# BuckAndOutputCircuits_Page_2.net
KiCad netlist of a schematic drawn in Altium Designer
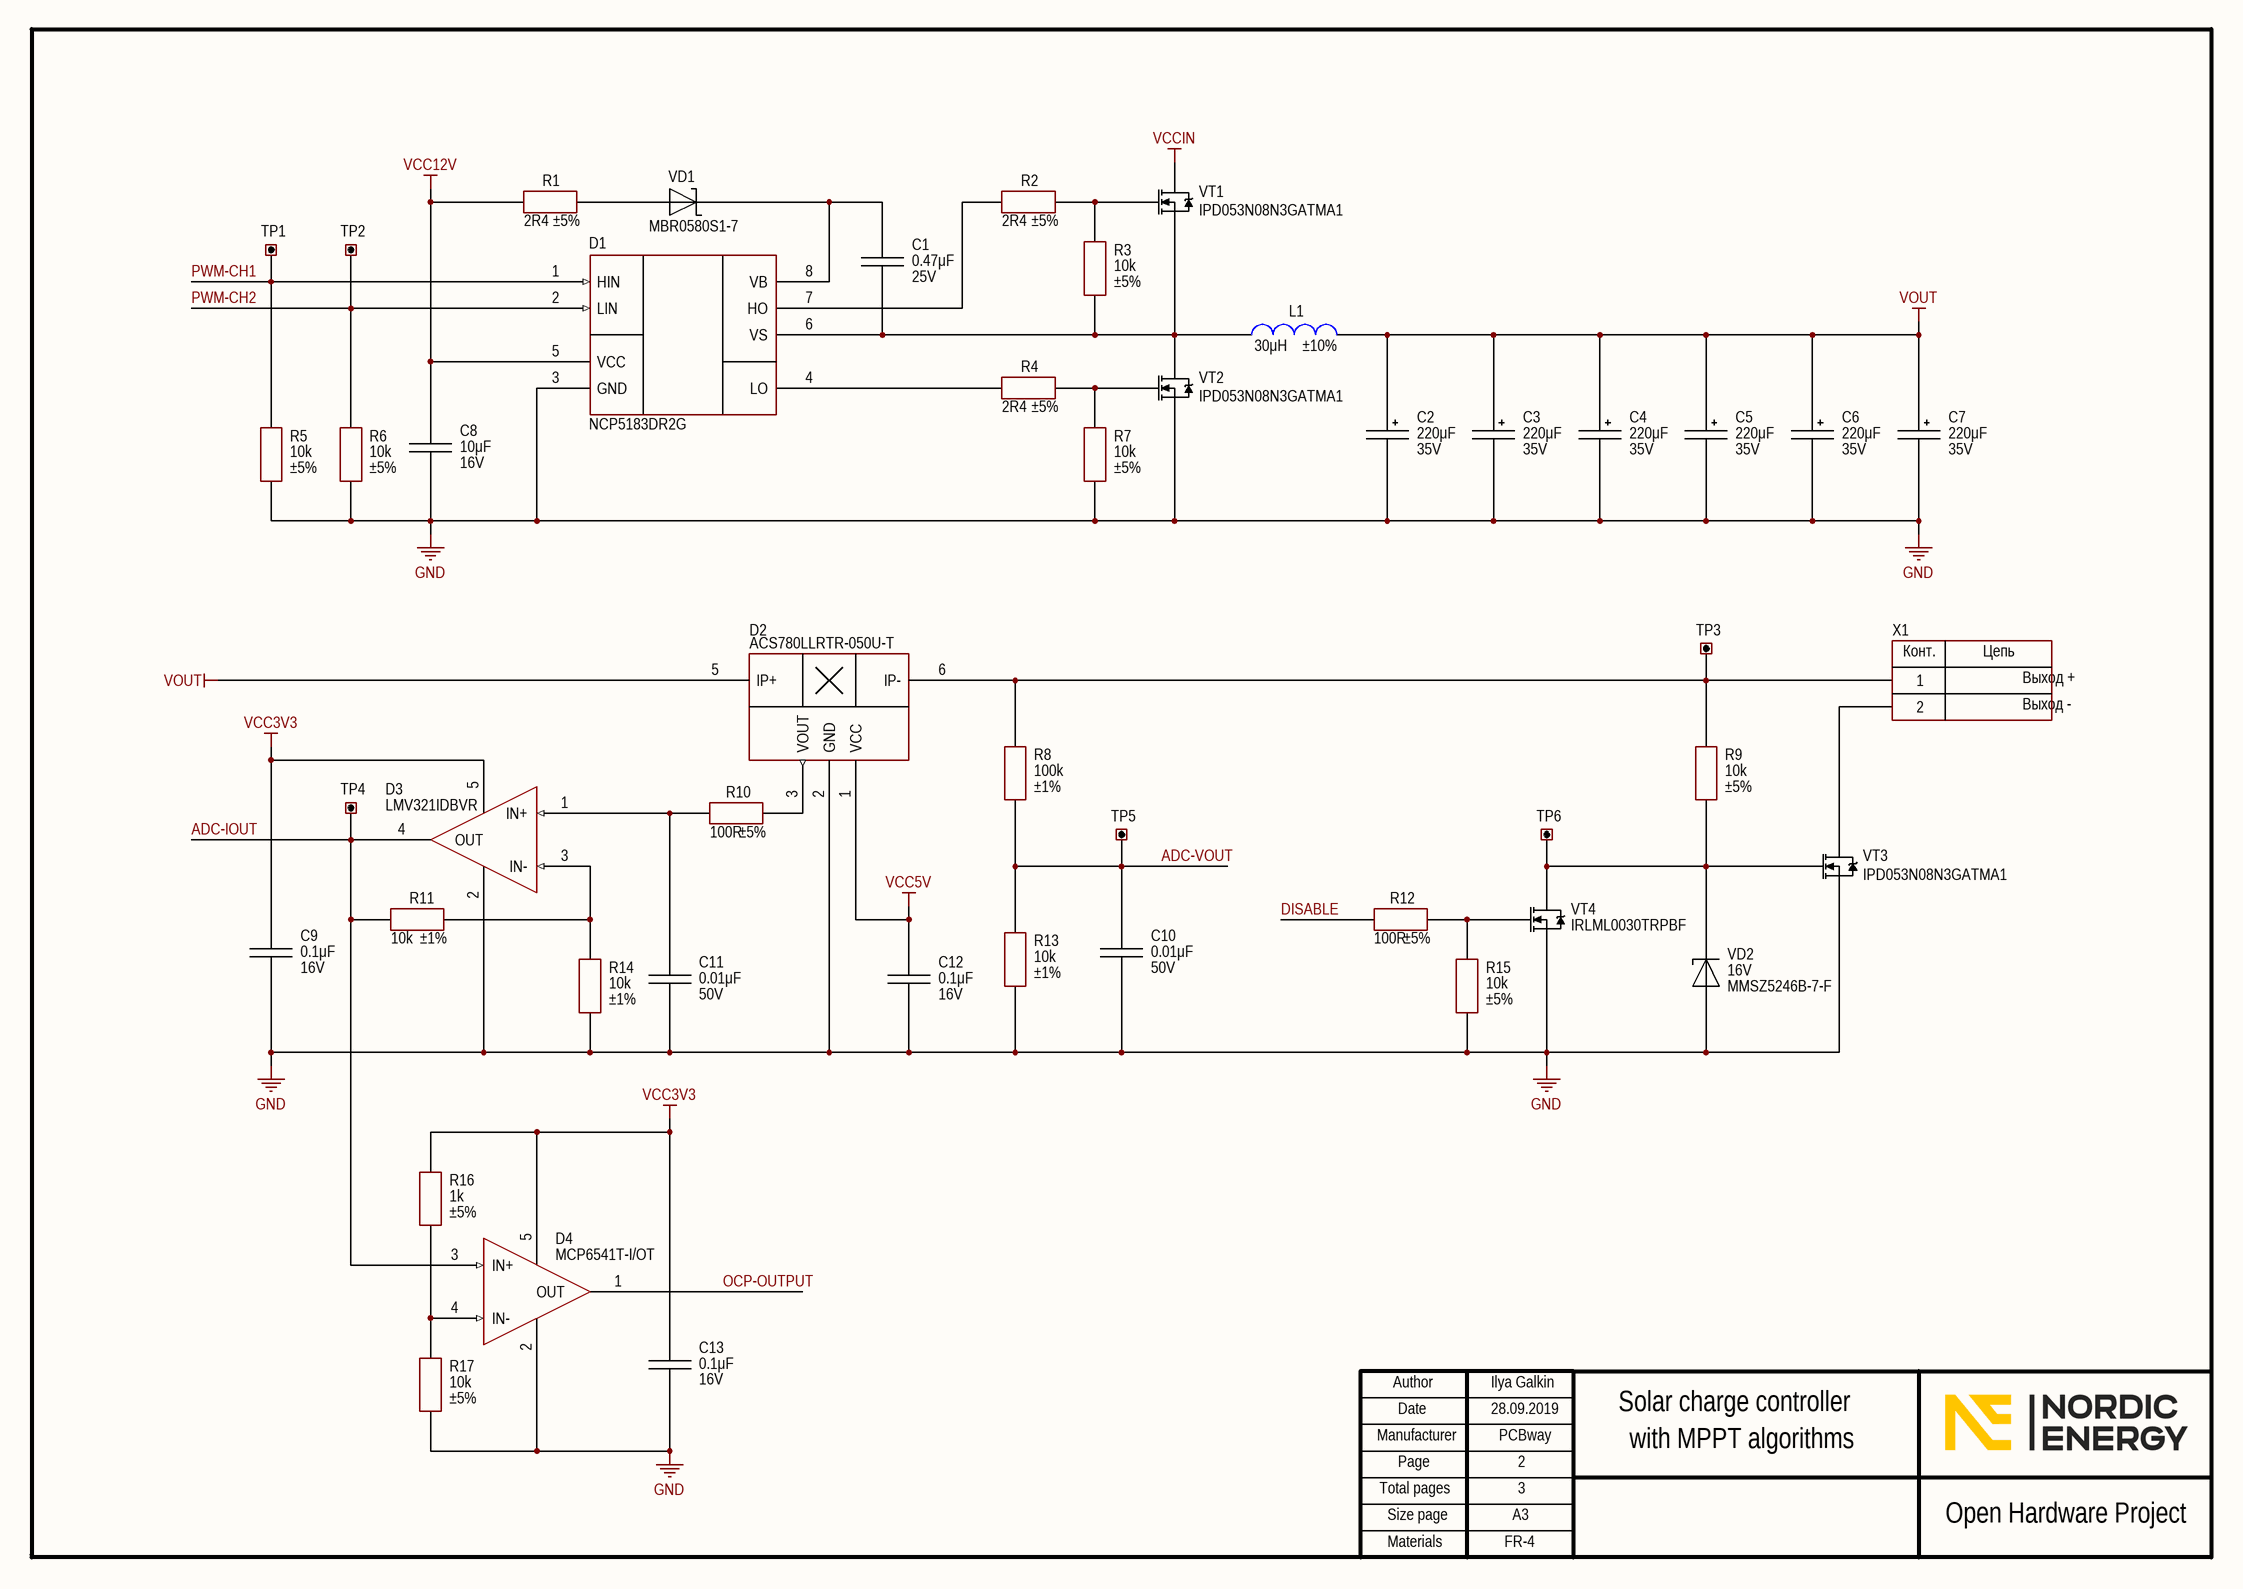
[diagram p0: BuckAndOutputCircuits. Page 2.SchDoc]

(export (version "E")
  (design (tool "Eeschema 10.0.6"))
  (components
    (comp (ref "C1")
      (value "0.47μF")
      (footprint "CAP: 0805")
      (fields
        (field (name "MANUFACTURER") "Yageo")
        (field (name "PARTNUMBER") "CC0805KKX7R8BB474")
        (field (name "VALUEMANUFACTURERPARTNUMBER") "Ceramic capacitor, 0.47μF, X7R, ±10%, 25V, 0805, -55...+125°C")
        (field (name "VOLTAGE") "25V")
      )
      (libsource (lib "Capacitor") (part "Ceramic_0805"))
    )
    (comp (ref "C2")
      (value "220μF")
      (footprint "CAP: D6.3C2.5H11")
      (fields
        (field (name "MANUFACTURER") "Aihua Group")
        (field (name "PARTNUMBER") "SPZ1VM221E12O00")
        (field (name "VALUEMANUFACTURERPARTNUMBER") "Aluminium polymer capacitor, 220μF, 35V, ±20%, 30mOhm, 12x6.3x2.5 mm, -55...+105°C")
        (field (name "VOLTAGE") "35V")
      )
      (libsource (lib "Capacitor") (part "Aluminium"))
    )
    (comp (ref "C3")
      (value "220μF")
      (footprint "CAP: D6.3C2.5H11")
      (fields
        (field (name "MANUFACTURER") "Aihua Group")
        (field (name "PARTNUMBER") "SPZ1VM221E12O00")
        (field (name "VALUEMANUFACTURERPARTNUMBER") "Aluminium polymer capacitor, 220μF, 35V, ±20%, 30mOhm, 12x6.3x2.5 mm, -55...+105°C")
        (field (name "VOLTAGE") "35V")
      )
      (libsource (lib "Capacitor") (part "Aluminium"))
    )
    (comp (ref "C4")
      (value "220μF")
      (footprint "CAP: D6.3C2.5H11")
      (fields
        (field (name "MANUFACTURER") "Aihua Group")
        (field (name "PARTNUMBER") "SPZ1VM221E12O00")
        (field (name "VALUEMANUFACTURERPARTNUMBER") "Aluminium polymer capacitor, 220μF, 35V, ±20%, 30mOhm, 12x6.3x2.5 mm, -55...+105°C")
        (field (name "VOLTAGE") "35V")
      )
      (libsource (lib "Capacitor") (part "Aluminium"))
    )
    (comp (ref "C5")
      (value "220μF")
      (footprint "CAP: D6.3C2.5H11")
      (fields
        (field (name "MANUFACTURER") "Aihua Group")
        (field (name "PARTNUMBER") "SPZ1VM221E12O00")
        (field (name "VALUEMANUFACTURERPARTNUMBER") "Aluminium polymer capacitor, 220μF, 35V, ±20%, 30mOhm, 12x6.3x2.5 mm, -55...+105°C")
        (field (name "VOLTAGE") "35V")
      )
      (libsource (lib "Capacitor") (part "Aluminium"))
    )
    (comp (ref "C6")
      (value "220μF")
      (footprint "CAP: D6.3C2.5H11")
      (fields
        (field (name "MANUFACTURER") "Aihua Group")
        (field (name "PARTNUMBER") "SPZ1VM221E12O00")
        (field (name "VALUEMANUFACTURERPARTNUMBER") "Aluminium polymer capacitor, 220μF, 35V, ±20%, 30mOhm, 12x6.3x2.5 mm, -55...+105°C")
        (field (name "VOLTAGE") "35V")
      )
      (libsource (lib "Capacitor") (part "Aluminium"))
    )
    (comp (ref "C7")
      (value "220μF")
      (footprint "CAP: D6.3C2.5H11")
      (fields
        (field (name "MANUFACTURER") "Aihua Group")
        (field (name "PARTNUMBER") "SPZ1VM221E12O00")
        (field (name "VALUEMANUFACTURERPARTNUMBER") "Aluminium polymer capacitor, 220μF, 35V, ±20%, 30mOhm, 12x6.3x2.5 mm, -55...+105°C")
        (field (name "VOLTAGE") "35V")
      )
      (libsource (lib "Capacitor") (part "Aluminium"))
    )
    (comp (ref "C8")
      (value "10μF")
      (footprint "CAP: 0805")
      (fields
        (field (name "MANUFACTURER") "Samsung")
        (field (name "PARTNUMBER") "CL21B106KOQNNNG")
        (field (name "VALUEMANUFACTURERPARTNUMBER") "Ceramic capacitor, 10μF, X7R, ±10%, 16V, 0805, -55...+125°C")
        (field (name "VOLTAGE") "16V")
      )
      (libsource (lib "Capacitor") (part "Ceramic_0805"))
    )
    (comp (ref "C9")
      (value "0.1μF")
      (footprint "CAP: 0805")
      (fields
        (field (name "MANUFACTURER") "Yageo")
        (field (name "PARTNUMBER") "CC0805KRX7R7BB104")
        (field (name "VALUEMANUFACTURERPARTNUMBER") "Ceramic capacitor, 0.1μF, X7R, ±10%, 16V, 0805, -55...+125°C")
        (field (name "VOLTAGE") "16V")
      )
      (libsource (lib "Capacitor") (part "Ceramic_0805"))
    )
    (comp (ref "C10")
      (value "0.01μF")
      (footprint "CAP: 0805")
      (fields
        (field (name "MANUFACTURER") "Yageo")
        (field (name "PARTNUMBER") "CC0805KRX7R9BB103")
        (field (name "VALUEMANUFACTURERPARTNUMBER") "Ceramic capacitor, 0.01μF, X7R, ±10%, 50V, 0805, -55...+125°C")
        (field (name "VOLTAGE") "50V")
      )
      (libsource (lib "Capacitor") (part "Ceramic_0805"))
    )
    (comp (ref "C11")
      (value "0.01μF")
      (footprint "CAP: 0805")
      (fields
        (field (name "MANUFACTURER") "Yageo")
        (field (name "PARTNUMBER") "CC0805KRX7R9BB103")
        (field (name "VALUEMANUFACTURERPARTNUMBER") "Ceramic capacitor, 0.01μF, X7R, ±10%, 50V, 0805, -55...+125°C")
        (field (name "VOLTAGE") "50V")
      )
      (libsource (lib "Capacitor") (part "Ceramic_0805"))
    )
    (comp (ref "C12")
      (value "0.1μF")
      (footprint "CAP: 0805")
      (fields
        (field (name "MANUFACTURER") "Yageo")
        (field (name "PARTNUMBER") "CC0805KRX7R7BB104")
        (field (name "VALUEMANUFACTURERPARTNUMBER") "Ceramic capacitor, 0.1μF, X7R, ±10%, 16V, 0805, -55...+125°C")
        (field (name "VOLTAGE") "16V")
      )
      (libsource (lib "Capacitor") (part "Ceramic_0805"))
    )
    (comp (ref "C13")
      (value "0.1μF")
      (footprint "CAP: 0805")
      (fields
        (field (name "MANUFACTURER") "Yageo")
        (field (name "PARTNUMBER") "CC0805KRX7R7BB104")
        (field (name "VALUEMANUFACTURERPARTNUMBER") "Ceramic capacitor, 0.1μF, X7R, ±10%, 16V, 0805, -55...+125°C")
        (field (name "VOLTAGE") "16V")
      )
      (libsource (lib "Capacitor") (part "Ceramic_0805"))
    )
    (comp (ref "D1")
      (value "~")
      (footprint "8-SOIC")
      (description "Gate driver")
      (fields
        (field (name "MANUFACTURER") "ON Semiconductor")
        (field (name "VALUEMANUFACTURERPARTNUMBER") "Half-bridge gate driver, 600V, 500kHz, ±4.3A, supply 9...18V, -40...+125°C, 8-SOIC")
        (field (name "PARTNUMBER") "NCP5183DR2G")
      )
      (libsource (lib "IC. Gate driver") (part "NCP5183DR2G"))
    )
    (comp (ref "D2")
      (value "~")
      (footprint "SENSOR: ACS781")
      (description "Current sensors")
      (fields
        (field (name "MANUFACTURER") "Allegro MicroSystems")
        (field (name "VALUEMANUFACTURERPARTNUMBER") "IC current sensors, 50A, ±1.5%, 120 kHz, 60mV/A, -40...+150°C, 7-PSOF")
        (field (name "PARTNUMBER") "ACS780LLRTR-050U-T")
      )
      (libsource (lib "IC. Sensor") (part "ACS780"))
    )
    (comp (ref "D3")
      (value "~")
      (footprint "SOT23-5")
      (description "OP amplifier")
      (fields
        (field (name "MANUFACTURER") "Texas Instruments")
        (field (name "VALUEMANUFACTURERPARTNUMBER") "IC op amplifier, Rail-to-Rail, 1 MHz, 2.7...5.5V, -40...+125°C, SOT23-5")
        (field (name "PARTNUMBER") "LMV321IDBVR")
      )
      (libsource (lib "IC. Amplifier") (part "LMV321IDBVR"))
    )
    (comp (ref "D4")
      (value "~")
      (footprint "SOT23-5")
      (description "Comparator")
      (fields
        (field (name "MANUFACTURER") "Microchip Technology")
        (field (name "VALUEMANUFACTURERPARTNUMBER") "IC comparator, Rail-to-Rail, 1.6...5.5V, -40...+85°C, SOT23-5")
        (field (name "PARTNUMBER") "MCP6541T-I/OT")
      )
      (libsource (lib "IC. Comparator") (part "MCP6541T-I/OT"))
    )
    (comp (ref "L1")
      (value "30μH")
      (footprint "IND: R32.8/20.1/10.7 (L)")
      (fields
        (field (name "MANUFACTURER") "Magnetics")
        (field (name "PARTNUMBER") "0077548A7")
        (field (name "VALUEMANUFACTURERPARTNUMBER") "Fixed inductor, 30μH, ±10%, R32.8/20.1/10.7, Kool Mu, µ=125, 127 нГн/витков2")
        (field (name "TOLERANCE") "±10%")
      )
      (libsource (lib "Inductor") (part "Inductor_R32.8/20.1/10.7"))
    )
    (comp (ref "R1")
      (value "2R4")
      (footprint "RES: 0805")
      (fields
        (field (name "MANUFACTURER") "Yageo")
        (field (name "PARTNUMBER") "RC0805JR-072R4L")
        (field (name "VALUEMANUFACTURERPARTNUMBER") "Resistor film, 2R4, ±5%, 0805, 0.125W, -55...+125°C")
        (field (name "TOLERANCE") "±5%")
      )
      (libsource (lib "") (part "Resistor_0805_1"))
    )
    (comp (ref "R2")
      (value "2R4")
      (footprint "RES: 0805")
      (fields
        (field (name "MANUFACTURER") "Yageo")
        (field (name "PARTNUMBER") "RC0805JR-072R4L")
        (field (name "VALUEMANUFACTURERPARTNUMBER") "Resistor film, 2R4, ±5%, 0805, 0.125W, -55...+125°C")
        (field (name "TOLERANCE") "±5%")
      )
      (libsource (lib "") (part "Resistor_0805_1"))
    )
    (comp (ref "R3")
      (value "10k")
      (footprint "RES: 0805")
      (fields
        (field (name "MANUFACTURER") "Yageo")
        (field (name "PARTNUMBER") "RC0805JR-0710KL")
        (field (name "VALUEMANUFACTURERPARTNUMBER") "Resistor film, 10k, ±5%, 0805, 0.125W, -55...+125°C")
        (field (name "TOLERANCE") "±5%")
      )
      (libsource (lib "Resistor") (part "Resistor_0805"))
    )
    (comp (ref "R4")
      (value "2R4")
      (footprint "RES: 0805")
      (fields
        (field (name "MANUFACTURER") "Yageo")
        (field (name "PARTNUMBER") "RC0805JR-072R4L")
        (field (name "VALUEMANUFACTURERPARTNUMBER") "Resistor film, 2R4, ±5%, 0805, 0.125W, -55...+125°C")
        (field (name "TOLERANCE") "±5%")
      )
      (libsource (lib "") (part "Resistor_0805_1"))
    )
    (comp (ref "R5")
      (value "10k")
      (footprint "RES: 0805")
      (fields
        (field (name "MANUFACTURER") "Yageo")
        (field (name "PARTNUMBER") "RC0805JR-0710KL")
        (field (name "VALUEMANUFACTURERPARTNUMBER") "Resistor film, 10k, ±5%, 0805, 0.125W, -55...+125°C")
        (field (name "TOLERANCE") "±5%")
      )
      (libsource (lib "Resistor") (part "Resistor_0805"))
    )
    (comp (ref "R6")
      (value "10k")
      (footprint "RES: 0805")
      (fields
        (field (name "MANUFACTURER") "Yageo")
        (field (name "PARTNUMBER") "RC0805JR-0710KL")
        (field (name "VALUEMANUFACTURERPARTNUMBER") "Resistor film, 10k, ±5%, 0805, 0.125W, -55...+125°C")
        (field (name "TOLERANCE") "±5%")
      )
      (libsource (lib "Resistor") (part "Resistor_0805"))
    )
    (comp (ref "R7")
      (value "10k")
      (footprint "RES: 0805")
      (fields
        (field (name "MANUFACTURER") "Yageo")
        (field (name "PARTNUMBER") "RC0805JR-0710KL")
        (field (name "VALUEMANUFACTURERPARTNUMBER") "Resistor film, 10k, ±5%, 0805, 0.125W, -55...+125°C")
        (field (name "TOLERANCE") "±5%")
      )
      (libsource (lib "Resistor") (part "Resistor_0805"))
    )
    (comp (ref "R8")
      (value "100k")
      (footprint "RES: 0805")
      (fields
        (field (name "MANUFACTURER") "Yageo")
        (field (name "PARTNUMBER") "RC0805FR-07100KL")
        (field (name "VALUEMANUFACTURERPARTNUMBER") "Resistor film, 100k, ±1%, 0805, 0.125W, -55...+125°C")
        (field (name "TOLERANCE") "±1%")
      )
      (libsource (lib "Resistor") (part "Resistor_0805"))
    )
    (comp (ref "R9")
      (value "10k")
      (footprint "RES: 0805")
      (fields
        (field (name "MANUFACTURER") "Yageo")
        (field (name "PARTNUMBER") "RC0805JR-0710KL")
        (field (name "VALUEMANUFACTURERPARTNUMBER") "Resistor film, 10k, ±5%, 0805, 0.125W, -55...+125°C")
        (field (name "TOLERANCE") "±5%")
      )
      (libsource (lib "Resistor") (part "Resistor_0805"))
    )
    (comp (ref "R10")
      (value "100R")
      (footprint "RES: 0805")
      (fields
        (field (name "MANUFACTURER") "Yageo")
        (field (name "PARTNUMBER") "RC0805JR-07100RL")
        (field (name "VALUEMANUFACTURERPARTNUMBER") "Resistor film, 100R, ±5%, 0805, 0.125W, -55...+125°C")
        (field (name "TOLERANCE") "±5%")
      )
      (libsource (lib "") (part "Resistor_0805_1"))
    )
    (comp (ref "R11")
      (value "10k")
      (footprint "RES: 0805")
      (fields
        (field (name "MANUFACTURER") "Yageo")
        (field (name "PARTNUMBER") "RC0805FR-0710KL")
        (field (name "VALUEMANUFACTURERPARTNUMBER") "Resistor film, 10k, ±1%, 0805, 0.125W, -55...+125°C")
        (field (name "TOLERANCE") "±1%")
      )
      (libsource (lib "") (part "Resistor_0805_1"))
    )
    (comp (ref "R12")
      (value "100R")
      (footprint "RES: 0805")
      (fields
        (field (name "MANUFACTURER") "Yageo")
        (field (name "PARTNUMBER") "RC0805JR-07100RL")
        (field (name "VALUEMANUFACTURERPARTNUMBER") "Resistor film, 100R, ±5%, 0805, 0.125W, -55...+125°C")
        (field (name "TOLERANCE") "±5%")
      )
      (libsource (lib "") (part "Resistor_0805_1"))
    )
    (comp (ref "R13")
      (value "10k")
      (footprint "RES: 0805")
      (fields
        (field (name "MANUFACTURER") "Yageo")
        (field (name "PARTNUMBER") "RC0805FR-0710KL")
        (field (name "VALUEMANUFACTURERPARTNUMBER") "Resistor film, 10k, ±1%, 0805, 0.125W, -55...+125°C")
        (field (name "TOLERANCE") "±1%")
      )
      (libsource (lib "Resistor") (part "Resistor_0805"))
    )
    (comp (ref "R14")
      (value "10k")
      (footprint "RES: 0805")
      (fields
        (field (name "MANUFACTURER") "Yageo")
        (field (name "PARTNUMBER") "RC0805FR-0710KL")
        (field (name "VALUEMANUFACTURERPARTNUMBER") "Resistor film, 10k, ±1%, 0805, 0.125W, -55...+125°C")
        (field (name "TOLERANCE") "±1%")
      )
      (libsource (lib "Resistor") (part "Resistor_0805"))
    )
    (comp (ref "R15")
      (value "10k")
      (footprint "RES: 0805")
      (fields
        (field (name "MANUFACTURER") "Yageo")
        (field (name "PARTNUMBER") "RC0805JR-0710KL")
        (field (name "VALUEMANUFACTURERPARTNUMBER") "Resistor film, 10k, ±5%, 0805, 0.125W, -55...+125°C")
        (field (name "TOLERANCE") "±5%")
      )
      (libsource (lib "Resistor") (part "Resistor_0805"))
    )
    (comp (ref "R16")
      (value "1k")
      (footprint "RES: 0805")
      (fields
        (field (name "MANUFACTURER") "Yageo")
        (field (name "PARTNUMBER") "RC0805JR-071KL")
        (field (name "VALUEMANUFACTURERPARTNUMBER") "Resistor film, 1k, ±5%, 0805, 0.125W, -55...+125°C")
        (field (name "TOLERANCE") "±5%")
      )
      (libsource (lib "Resistor") (part "Resistor_0805"))
    )
    (comp (ref "R17")
      (value "10k")
      (footprint "RES: 0805")
      (fields
        (field (name "MANUFACTURER") "Yageo")
        (field (name "PARTNUMBER") "RC0805JR-0710KL")
        (field (name "VALUEMANUFACTURERPARTNUMBER") "Resistor film, 10k, ±5%, 0805, 0.125W, -55...+125°C")
        (field (name "TOLERANCE") "±5%")
      )
      (libsource (lib "Resistor") (part "Resistor_0805"))
    )
    (comp (ref "TP1")
      (value "~")
      (footprint "CON: 5001 (Keystone)")
      (fields
        (field (name "MANUFACTURER") "Keystone")
        (field (name "VALUEMANUFACTURERPARTNUMBER") "Test point, Keystone, 5001")
        (field (name "PARTNUMBER") "5001")
      )
      (libsource (lib "Connector") (part "Connector_Test_Point"))
    )
    (comp (ref "TP2")
      (value "~")
      (footprint "CON: 5001 (Keystone)")
      (fields
        (field (name "MANUFACTURER") "Keystone")
        (field (name "VALUEMANUFACTURERPARTNUMBER") "Test point, Keystone, 5001")
        (field (name "PARTNUMBER") "5001")
      )
      (libsource (lib "Connector") (part "Connector_Test_Point"))
    )
    (comp (ref "TP3")
      (value "~")
      (footprint "CON: 5001 (Keystone)")
      (fields
        (field (name "MANUFACTURER") "Keystone")
        (field (name "VALUEMANUFACTURERPARTNUMBER") "Test point, Keystone, 5001")
        (field (name "PARTNUMBER") "5001")
      )
      (libsource (lib "Connector") (part "Connector_Test_Point"))
    )
    (comp (ref "TP4")
      (value "~")
      (footprint "CON: 5004 (Keystone)")
      (fields
        (field (name "MANUFACTURER") "Keystone")
        (field (name "VALUEMANUFACTURERPARTNUMBER") "Test point, Keystone, 5001")
        (field (name "PARTNUMBER") "5001")
      )
      (libsource (lib "Connector") (part "Connector_Test_Point"))
    )
    (comp (ref "TP5")
      (value "~")
      (footprint "CON: 5004 (Keystone)")
      (fields
        (field (name "MANUFACTURER") "Keystone")
        (field (name "VALUEMANUFACTURERPARTNUMBER") "Test point, Keystone, 5001")
        (field (name "PARTNUMBER") "5001")
      )
      (libsource (lib "Connector") (part "Connector_Test_Point"))
    )
    (comp (ref "TP6")
      (value "~")
      (footprint "CON: 5001 (Keystone)")
      (fields
        (field (name "MANUFACTURER") "Keystone")
        (field (name "VALUEMANUFACTURERPARTNUMBER") "Test point, Keystone, 5001")
        (field (name "PARTNUMBER") "5001")
      )
      (libsource (lib "Connector") (part "Connector_Test_Point"))
    )
    (comp (ref "VD1")
      (value "~")
      (footprint "DIODE: SOD123")
      (fields
        (field (name "MANUFACTURER") "Diodes Incorporated")
        (field (name "VALUEMANUFACTURERPARTNUMBER") "Schottky diode, 80V, 500mA, 1V, 15pF, SOD-123, -55...+150°C")
        (field (name "VOLTAGE") "80V")
        (field (name "PARTNUMBER") "MBR0580S1-7")
      )
      (libsource (lib "Diode") (part "Schottky_single"))
    )
    (comp (ref "VD2")
      (value "~")
      (footprint "DIODE: SOD123")
      (fields
        (field (name "MANUFACTURER") "Diodes Incorporated")
        (field (name "VALUEMANUFACTURERPARTNUMBER") "Zener diode, 16V, 500mW, 0.9V, 17Ohm, SOD-123, -65...+150°C")
        (field (name "VOLTAGE") "16V")
        (field (name "PARTNUMBER") "MMSZ5246B-7-F")
      )
      (libsource (lib "Diode") (part "Zener_single"))
    )
    (comp (ref "VT1")
      (value "~")
      (footprint "DPAK")
      (fields
        (field (name "MANUFACTURER") "Infineon Technologies")
        (field (name "VALUEMANUFACTURERPARTNUMBER") "MOSFET N-channel transistor, 80V, 90A, 69nC, 150W, 5.3mOhm, 4750pF, Dpak, -55...+150°C")
        (field (name "PARTNUMBER") "IPD053N08N3GATMA1")
      )
      (libsource (lib "Transistor") (part "MOSFET_N_132"))
    )
    (comp (ref "VT2")
      (value "~")
      (footprint "DPAK")
      (fields
        (field (name "MANUFACTURER") "Infineon Technologies")
        (field (name "VALUEMANUFACTURERPARTNUMBER") "MOSFET N-channel transistor, 80V, 90A, 69nC, 150W, 5.3mOhm, 4750pF, Dpak, -55...+150°C")
        (field (name "PARTNUMBER") "IPD053N08N3GATMA1")
      )
      (libsource (lib "Transistor") (part "MOSFET_N_132"))
    )
    (comp (ref "VT3")
      (value "~")
      (footprint "DPAK")
      (fields
        (field (name "MANUFACTURER") "Infineon Technologies")
        (field (name "VALUEMANUFACTURERPARTNUMBER") "MOSFET N-channel transistor, 80V, 90A, 69nC, 150W, 5.3mOhm, 4750pF, Dpak, -55...+150°C")
        (field (name "PARTNUMBER") "IPD053N08N3GATMA1")
      )
      (libsource (lib "Transistor") (part "MOSFET_N_132"))
    )
    (comp (ref "VT4")
      (value "~")
      (footprint "SOT23")
      (fields
        (field (name "MANUFACTURER") "Infineon Technologies")
        (field (name "VALUEMANUFACTURERPARTNUMBER") "MOSFET N-channel transistor, 30V, 5.3A, 2.6nC, 2.5W, 27mOhm, 382pF, SOT-23, -55...+150°C")
        (field (name "PARTNUMBER") "IRLML0030TRPBF")
      )
      (libsource (lib "Transistor") (part "MOSFET_N_132"))
    )
    (comp (ref "X1")
      (value "~")
      (footprint "CON: 6PCV-02-006")
      (fields
        (field (name "MANUFACTURER") "TE Connectivity")
        (field (name "VALUEMANUFACTURERPARTNUMBER") "Connector, 2pin, 9.53mm, 300VAC, 25A")
        (field (name "PARTNUMBER") "6PCV-02-006")
      )
      (libsource (lib "Connector") (part "Connector_6PCV-02"))
    )
  )
  (nets
    (net (code "1") (name "/ADC-IOUT") (class "Default")
      (node (ref "D3") (pin "4") (pinfunction "OUT_4") (pintype "power_in"))
      (node (ref "D4") (pin "3") (pinfunction "IN+_3") (pintype "input"))
      (node (ref "R11") (pin "1") (pinfunction "1_1") (pintype "passive"))
      (node (ref "TP4") (pin "1") (pinfunction "1_1") (pintype "passive"))
    )
    (net (code "2") (name "/ADC-VOUT") (class "Default")
      (node (ref "C10") (pin "2") (pinfunction "2_2") (pintype "power_in"))
      (node (ref "R13") (pin "1") (pinfunction "1_1") (pintype "passive"))
      (node (ref "R8") (pin "2") (pinfunction "2_2") (pintype "passive"))
      (node (ref "TP5") (pin "1") (pinfunction "1_1") (pintype "passive"))
    )
    (net (code "3") (name "/DISABLE") (class "Default")
      (node (ref "R12") (pin "1") (pinfunction "1_1") (pintype "passive"))
    )
    (net (code "4") (name "/OCP-OUTPUT") (class "Default")
      (node (ref "D4") (pin "1") (pinfunction "OUT_1") (pintype "power_in"))
    )
    (net (code "5") (name "/PWM-CH1") (class "Default")
      (node (ref "D1") (pin "1") (pinfunction "HIN_1") (pintype "input"))
      (node (ref "R5") (pin "1") (pinfunction "1_1") (pintype "passive"))
      (node (ref "TP1") (pin "1") (pinfunction "1_1") (pintype "passive"))
    )
    (net (code "6") (name "/PWM-CH2") (class "Default")
      (node (ref "D1") (pin "2") (pinfunction "LIN_2") (pintype "input"))
      (node (ref "R6") (pin "1") (pinfunction "1_1") (pintype "passive"))
      (node (ref "TP2") (pin "1") (pinfunction "1_1") (pintype "passive"))
    )
    (net (code "7") (name "GND") (class "Default")
      (node (ref "C10") (pin "1") (pinfunction "1_1") (pintype "power_in"))
      (node (ref "C11") (pin "1") (pinfunction "1_1") (pintype "power_in"))
      (node (ref "C12") (pin "1") (pinfunction "1_1") (pintype "power_in"))
      (node (ref "C13") (pin "1") (pinfunction "1_1") (pintype "power_in"))
      (node (ref "C2") (pin "2") (pinfunction "2_2") (pintype "power_in"))
      (node (ref "C3") (pin "2") (pinfunction "2_2") (pintype "power_in"))
      (node (ref "C4") (pin "2") (pinfunction "2_2") (pintype "power_in"))
      (node (ref "C5") (pin "2") (pinfunction "2_2") (pintype "power_in"))
      (node (ref "C6") (pin "2") (pinfunction "2_2") (pintype "power_in"))
      (node (ref "C7") (pin "2") (pinfunction "2_2") (pintype "power_in"))
      (node (ref "C8") (pin "1") (pinfunction "1_1") (pintype "power_in"))
      (node (ref "C9") (pin "1") (pinfunction "1_1") (pintype "power_in"))
      (node (ref "D1") (pin "3") (pinfunction "GND_3") (pintype "passive"))
      (node (ref "D2") (pin "2") (pinfunction "GND_2") (pintype "passive"))
      (node (ref "D3") (pin "2") (pinfunction "V-_2") (pintype "power_in"))
      (node (ref "D4") (pin "2") (pinfunction "V-_2") (pintype "power_in"))
      (node (ref "R13") (pin "2") (pinfunction "2_2") (pintype "passive"))
      (node (ref "R14") (pin "2") (pinfunction "2_2") (pintype "passive"))
      (node (ref "R15") (pin "2") (pinfunction "2_2") (pintype "passive"))
      (node (ref "R17") (pin "2") (pinfunction "2_2") (pintype "passive"))
      (node (ref "R5") (pin "2") (pinfunction "2_2") (pintype "passive"))
      (node (ref "R6") (pin "2") (pinfunction "2_2") (pintype "passive"))
      (node (ref "R7") (pin "2") (pinfunction "2_2") (pintype "passive"))
      (node (ref "VD2") (pin "1") (pinfunction "A_1") (pintype "passive"))
      (node (ref "VT2") (pin "2") (pinfunction "S_2") (pintype "passive"))
      (node (ref "VT3") (pin "2") (pinfunction "S_2") (pintype "passive"))
      (node (ref "VT4") (pin "2") (pinfunction "S_2") (pintype "passive"))
    )
    (net (code "8") (name "Net-(D1-HO)") (class "Default")
      (node (ref "D1") (pin "7") (pinfunction "HO_7") (pintype "passive"))
      (node (ref "R2") (pin "1") (pinfunction "1_1") (pintype "passive"))
    )
    (net (code "9") (name "Net-(D1-LO)") (class "Default")
      (node (ref "D1") (pin "4") (pinfunction "LO_4") (pintype "passive"))
      (node (ref "R4") (pin "1") (pinfunction "1_1") (pintype "passive"))
    )
    (net (code "10") (name "Net-(D1-VB)") (class "Default")
      (node (ref "C1") (pin "2") (pinfunction "2_2") (pintype "power_in"))
      (node (ref "D1") (pin "8") (pinfunction "VB_8") (pintype "passive"))
      (node (ref "VD1") (pin "2") (pinfunction "2_2") (pintype "passive"))
    )
    (net (code "11") (name "Net-(D1-VS)") (class "Default")
      (node (ref "C1") (pin "1") (pinfunction "1_1") (pintype "power_in"))
      (node (ref "D1") (pin "6") (pinfunction "VS_6") (pintype "passive"))
      (node (ref "L1") (pin "2") (pinfunction "2_2") (pintype "passive"))
      (node (ref "R3") (pin "2") (pinfunction "2_2") (pintype "passive"))
      (node (ref "VT1") (pin "2") (pinfunction "S_2") (pintype "passive"))
      (node (ref "VT2") (pin "3") (pinfunction "D_3") (pintype "passive"))
    )
    (net (code "12") (name "Net-(D2-IP-)") (class "Default")
      (node (ref "D2") (pin "6") (pinfunction "IP-_6") (pintype "passive"))
      (node (ref "R8") (pin "1") (pinfunction "1_1") (pintype "passive"))
      (node (ref "R9") (pin "1") (pinfunction "1_1") (pintype "passive"))
      (node (ref "TP3") (pin "1") (pinfunction "1_1") (pintype "passive"))
      (node (ref "X1") (pin "1") (pinfunction "1_1") (pintype "passive"))
    )
    (net (code "13") (name "Net-(D2-VOUT)") (class "Default")
      (node (ref "D2") (pin "3") (pinfunction "VOUT_3") (pintype "output"))
      (node (ref "R10") (pin "2") (pinfunction "2_2") (pintype "passive"))
    )
    (net (code "14") (name "Net-(D3-IN+)") (class "Default")
      (node (ref "C11") (pin "2") (pinfunction "2_2") (pintype "power_in"))
      (node (ref "D3") (pin "1") (pinfunction "IN+_1") (pintype "input"))
      (node (ref "R10") (pin "1") (pinfunction "1_1") (pintype "passive"))
    )
    (net (code "15") (name "Net-(D3-IN-)") (class "Default")
      (node (ref "D3") (pin "3") (pinfunction "IN-_3") (pintype "input"))
      (node (ref "R11") (pin "2") (pinfunction "2_2") (pintype "passive"))
      (node (ref "R14") (pin "1") (pinfunction "1_1") (pintype "passive"))
    )
    (net (code "16") (name "Net-(D4-IN-)") (class "Default")
      (node (ref "D4") (pin "4") (pinfunction "IN-_4") (pintype "input"))
      (node (ref "R16") (pin "2") (pinfunction "2_2") (pintype "passive"))
      (node (ref "R17") (pin "1") (pinfunction "1_1") (pintype "passive"))
    )
    (net (code "17") (name "Net-(R1-Pad2)") (class "Default")
      (node (ref "R1") (pin "2") (pinfunction "2_2") (pintype "passive"))
      (node (ref "VD1") (pin "1") (pinfunction "1_1") (pintype "passive"))
    )
    (net (code "18") (name "Net-(VD2-C)") (class "Default")
      (node (ref "R9") (pin "2") (pinfunction "2_2") (pintype "passive"))
      (node (ref "TP6") (pin "1") (pinfunction "1_1") (pintype "passive"))
      (node (ref "VD2") (pin "2") (pinfunction "C_2") (pintype "passive"))
      (node (ref "VT3") (pin "1") (pinfunction "G_1") (pintype "passive"))
      (node (ref "VT4") (pin "3") (pinfunction "D_3") (pintype "passive"))
    )
    (net (code "19") (name "Net-(VT1-G)") (class "Default")
      (node (ref "R2") (pin "2") (pinfunction "2_2") (pintype "passive"))
      (node (ref "R3") (pin "1") (pinfunction "1_1") (pintype "passive"))
      (node (ref "VT1") (pin "1") (pinfunction "G_1") (pintype "passive"))
    )
    (net (code "20") (name "Net-(VT2-G)") (class "Default")
      (node (ref "R4") (pin "2") (pinfunction "2_2") (pintype "passive"))
      (node (ref "R7") (pin "1") (pinfunction "1_1") (pintype "passive"))
      (node (ref "VT2") (pin "1") (pinfunction "G_1") (pintype "passive"))
    )
    (net (code "21") (name "Net-(VT3-D)") (class "Default")
      (node (ref "VT3") (pin "3") (pinfunction "D_3") (pintype "passive"))
      (node (ref "X1") (pin "2") (pinfunction "2_2") (pintype "passive"))
    )
    (net (code "22") (name "Net-(VT4-G)") (class "Default")
      (node (ref "R12") (pin "2") (pinfunction "2_2") (pintype "passive"))
      (node (ref "R15") (pin "1") (pinfunction "1_1") (pintype "passive"))
      (node (ref "VT4") (pin "1") (pinfunction "G_1") (pintype "passive"))
    )
    (net (code "23") (name "VCC3V3") (class "Default")
      (node (ref "C13") (pin "2") (pinfunction "2_2") (pintype "power_in"))
      (node (ref "C9") (pin "2") (pinfunction "2_2") (pintype "power_in"))
      (node (ref "D3") (pin "5") (pinfunction "V+_5") (pintype "power_in"))
      (node (ref "D4") (pin "5") (pinfunction "V+_5") (pintype "power_in"))
      (node (ref "R16") (pin "1") (pinfunction "1_1") (pintype "passive"))
    )
    (net (code "24") (name "VCC5V") (class "Default")
      (node (ref "C12") (pin "2") (pinfunction "2_2") (pintype "power_in"))
      (node (ref "D2") (pin "1") (pinfunction "VCC_1") (pintype "passive"))
    )
    (net (code "25") (name "VCC12V") (class "Default")
      (node (ref "C8") (pin "2") (pinfunction "2_2") (pintype "power_in"))
      (node (ref "D1") (pin "5") (pinfunction "VCC_5") (pintype "passive"))
      (node (ref "R1") (pin "1") (pinfunction "1_1") (pintype "passive"))
    )
    (net (code "26") (name "VCCIN") (class "Default")
      (node (ref "VT1") (pin "3") (pinfunction "D_3") (pintype "passive"))
    )
    (net (code "27") (name "VOUT") (class "Default")
      (node (ref "C2") (pin "1") (pinfunction "1_1") (pintype "power_in"))
      (node (ref "C3") (pin "1") (pinfunction "1_1") (pintype "power_in"))
      (node (ref "C4") (pin "1") (pinfunction "1_1") (pintype "power_in"))
      (node (ref "C5") (pin "1") (pinfunction "1_1") (pintype "power_in"))
      (node (ref "C6") (pin "1") (pinfunction "1_1") (pintype "power_in"))
      (node (ref "C7") (pin "1") (pinfunction "1_1") (pintype "power_in"))
      (node (ref "D2") (pin "5") (pinfunction "IP+_5") (pintype "passive"))
      (node (ref "L1") (pin "1") (pinfunction "1_1") (pintype "passive"))
    )
  )
)
